# ECG_Schematic.net
KiCad netlist of a schematic drawn in Altium Designer
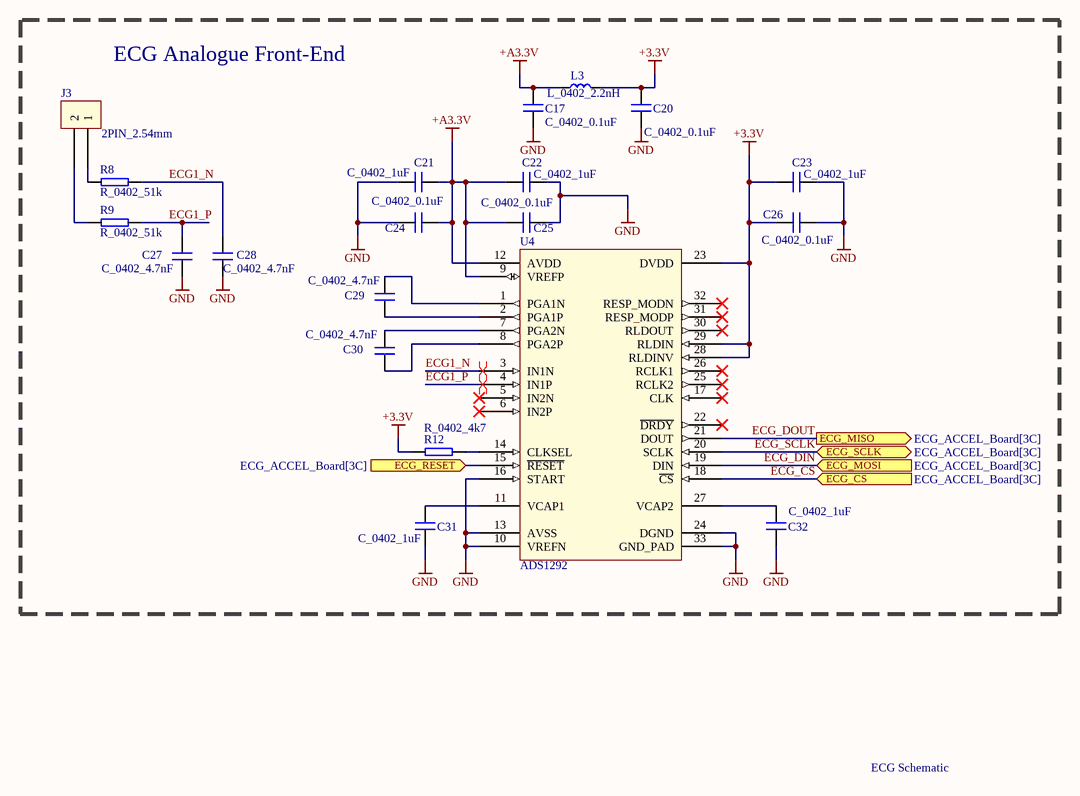
[diagram p0: ECG_Schematic.SchDoc]

(export (version "E")
  (design (tool "Eeschema 10.0.6"))
  (components
    (comp (ref "C17")
      (value "C_0402_0.1uF")
      (footprint "C_0402")
      (fields (field (name "JLC PART NUMBER") "C1525"))
      (libsource (lib "Petar B") (part "Cap_symbol"))
    )
    (comp (ref "C20")
      (value "C_0402_0.1uF")
      (footprint "C_0402")
      (fields (field (name "JLC PART NUMBER") "C1525"))
      (libsource (lib "Petar B") (part "Cap_symbol"))
    )
    (comp (ref "C21")
      (value "C_0402_1uF")
      (footprint "C_0402")
      (fields (field (name "JLC PART NUMBER") "C52923"))
      (libsource (lib "Petar B") (part "Cap_symbol"))
    )
    (comp (ref "C22")
      (value "C_0402_1uF")
      (footprint "C_0402")
      (fields (field (name "JLC PART NUMBER") "C52923"))
      (libsource (lib "Petar B") (part "Cap_symbol"))
    )
    (comp (ref "C23")
      (value "C_0402_1uF")
      (footprint "C_0402")
      (fields (field (name "JLC PART NUMBER") "C52923"))
      (libsource (lib "Petar B") (part "Cap_symbol"))
    )
    (comp (ref "C24")
      (value "C_0402_0.1uF")
      (footprint "C_0402")
      (fields (field (name "JLC PART NUMBER") "C1525"))
      (libsource (lib "Petar B") (part "Cap_symbol"))
    )
    (comp (ref "C25")
      (value "C_0402_0.1uF")
      (footprint "C_0402")
      (fields (field (name "JLC PART NUMBER") "C1525"))
      (libsource (lib "Petar B") (part "Cap_symbol"))
    )
    (comp (ref "C26")
      (value "C_0402_0.1uF")
      (footprint "C_0402")
      (fields (field (name "JLC PART NUMBER") "C1525"))
      (libsource (lib "Petar B") (part "Cap_symbol"))
    )
    (comp (ref "C27")
      (value "C_0402_4.7nF")
      (footprint "C_0402")
      (fields (field (name "JLC PART NUMBER") "C1538"))
      (libsource (lib "Petar B") (part "Cap_symbol"))
    )
    (comp (ref "C28")
      (value "C_0402_4.7nF")
      (footprint "C_0402")
      (fields (field (name "JLC PART NUMBER") "C1538"))
      (libsource (lib "Petar B") (part "Cap_symbol"))
    )
    (comp (ref "C29")
      (value "C_0402_4.7nF")
      (footprint "C_0402")
      (fields (field (name "JLC PART NUMBER") "C1538"))
      (libsource (lib "Petar B") (part "Cap_symbol"))
    )
    (comp (ref "C30")
      (value "C_0402_4.7nF")
      (footprint "C_0402")
      (fields (field (name "JLC PART NUMBER") "C1538"))
      (libsource (lib "Petar B") (part "Cap_symbol"))
    )
    (comp (ref "C31")
      (value "C_0402_1uF")
      (footprint "C_0402")
      (fields (field (name "JLC PART NUMBER") "C52923"))
      (libsource (lib "Petar B") (part "Cap_symbol"))
    )
    (comp (ref "C32")
      (value "C_0402_1uF")
      (footprint "C_0402")
      (fields (field (name "JLC PART NUMBER") "C52923"))
      (libsource (lib "Petar B") (part "Cap_symbol"))
    )
    (comp (ref "J3")
      (value "2PIN_2.54mm")
      (footprint "2PIN_2.54mm-Footprint-1")
      (description "2 pin power input")
      (fields (field (name "JLC PART NUMBER") "C5360898"))
      (libsource (lib "Petar B") (part "2PIN_2.54mm-Symbol-1"))
    )
    (comp (ref "L3")
      (value "L_0402_2.2nH")
      (footprint "L_0402")
      (fields (field (name "JLC PART NUMBER") "C92035"))
      (libsource (lib "Petar B") (part "Ind_Symbol"))
    )
    (comp (ref "R8")
      (value "R_0402_51k")
      (footprint "R_0402")
      (fields (field (name "JLC PART NUMBER") "C25794"))
      (libsource (lib "Petar B") (part "R_symbol"))
    )
    (comp (ref "R9")
      (value "R_0402_51k")
      (footprint "R_0402")
      (fields (field (name "JLC PART NUMBER") "C25794"))
      (libsource (lib "Petar B") (part "R_symbol"))
    )
    (comp (ref "R12")
      (value "R_0402_4k7")
      (footprint "R_0402")
      (fields (field (name "JLC PART NUMBER") "C25900"))
      (libsource (lib "Petar B") (part "R_symbol"))
    )
    (comp (ref "U4")
      (value "ADS1292")
      (footprint "QFN127P600-8N")
      (description "ECG Analog Front End - AFE 2-Channel,24B ADC")
      (fields (field (name "JLC PART NUMBER") "C456281"))
      (libsource (lib "Petar B") (part "ADS1292-Symbol-1"))
    )
  )
  (nets
    (net (code "1") (name "+3.3V") (class "Default")
      (node (ref "C20") (pin "2") (pinfunction "2_2") (pintype "passive"))
      (node (ref "C23") (pin "1") (pinfunction "1_1") (pintype "passive"))
      (node (ref "C26") (pin "1") (pinfunction "1_1") (pintype "passive"))
      (node (ref "L3") (pin "2") (pinfunction "2_2") (pintype "passive"))
      (node (ref "R12") (pin "2") (pinfunction "2_2") (pintype "passive"))
      (node (ref "U4") (pin "23") (pinfunction "DVDD_23") (pintype "power_in"))
      (node (ref "U4") (pin "28") (pinfunction "RLDINV_28") (pintype "input"))
      (node (ref "U4") (pin "29") (pinfunction "RLDIN_29") (pintype "input"))
    )
    (net (code "2") (name "+A3.3V") (class "Default")
      (node (ref "C17") (pin "2") (pinfunction "2_2") (pintype "passive"))
      (node (ref "C21") (pin "2") (pinfunction "2_2") (pintype "passive"))
      (node (ref "C22") (pin "2") (pinfunction "2_2") (pintype "passive"))
      (node (ref "C24") (pin "2") (pinfunction "2_2") (pintype "passive"))
      (node (ref "C25") (pin "2") (pinfunction "2_2") (pintype "passive"))
      (node (ref "L3") (pin "1") (pinfunction "1_1") (pintype "passive"))
      (node (ref "U4") (pin "12") (pinfunction "AVDD_12") (pintype "power_in"))
      (node (ref "U4") (pin "9") (pinfunction "VREFP_9") (pintype "bidirectional"))
    )
    (net (code "3") (name "/ECG1_N") (class "Default")
      (node (ref "C28") (pin "2") (pinfunction "2_2") (pintype "passive"))
      (node (ref "R8") (pin "1") (pinfunction "1_1") (pintype "passive"))
      (node (ref "U4") (pin "3") (pinfunction "IN1N_3") (pintype "input"))
    )
    (net (code "4") (name "/ECG1_P") (class "Default")
      (node (ref "C27") (pin "2") (pinfunction "2_2") (pintype "passive"))
      (node (ref "R9") (pin "1") (pinfunction "1_1") (pintype "passive"))
      (node (ref "U4") (pin "4") (pinfunction "IN1P_4") (pintype "input"))
    )
    (net (code "5") (name "/ECG_CS") (class "Default")
      (node (ref "U4") (pin "18") (pinfunction "~{CS}_18") (pintype "input"))
    )
    (net (code "6") (name "/ECG_DIN") (class "Default")
      (node (ref "U4") (pin "19") (pinfunction "DIN_19") (pintype "input"))
    )
    (net (code "7") (name "/ECG_DOUT") (class "Default")
      (node (ref "U4") (pin "21") (pinfunction "DOUT_21") (pintype "output"))
    )
    (net (code "8") (name "/ECG_RESET") (class "Default")
      (node (ref "U4") (pin "15") (pinfunction "~{RESET}_15") (pintype "input"))
    )
    (net (code "9") (name "/ECG_SCLK") (class "Default")
      (node (ref "U4") (pin "20") (pinfunction "SCLK_20") (pintype "input"))
    )
    (net (code "10") (name "GND") (class "Default")
      (node (ref "C17") (pin "1") (pinfunction "1_1") (pintype "passive"))
      (node (ref "C20") (pin "1") (pinfunction "1_1") (pintype "passive"))
      (node (ref "C21") (pin "1") (pinfunction "1_1") (pintype "passive"))
      (node (ref "C22") (pin "1") (pinfunction "1_1") (pintype "passive"))
      (node (ref "C23") (pin "2") (pinfunction "2_2") (pintype "passive"))
      (node (ref "C24") (pin "1") (pinfunction "1_1") (pintype "passive"))
      (node (ref "C25") (pin "1") (pinfunction "1_1") (pintype "passive"))
      (node (ref "C26") (pin "2") (pinfunction "2_2") (pintype "passive"))
      (node (ref "C27") (pin "1") (pinfunction "1_1") (pintype "passive"))
      (node (ref "C28") (pin "1") (pinfunction "1_1") (pintype "passive"))
      (node (ref "C31") (pin "1") (pinfunction "1_1") (pintype "passive"))
      (node (ref "C32") (pin "1") (pinfunction "1_1") (pintype "passive"))
      (node (ref "U4") (pin "10") (pinfunction "VREFN_10") (pintype "power_in"))
      (node (ref "U4") (pin "13") (pinfunction "AVSS_13") (pintype "power_in"))
      (node (ref "U4") (pin "16") (pinfunction "START_16") (pintype "input"))
      (node (ref "U4") (pin "24") (pinfunction "DGND_24") (pintype "power_in"))
      (node (ref "U4") (pin "33") (pinfunction "GND_PAD_33") (pintype "power_in"))
    )
    (net (code "11") (name "Net-(J3-Pad1)") (class "Default")
      (node (ref "J3") (pin "1") (pinfunction "1_1") (pintype "passive"))
      (node (ref "R8") (pin "2") (pinfunction "2_2") (pintype "passive"))
    )
    (net (code "12") (name "Net-(J3-Pad2)") (class "Default")
      (node (ref "J3") (pin "2") (pinfunction "2_2") (pintype "passive"))
      (node (ref "R9") (pin "2") (pinfunction "2_2") (pintype "passive"))
    )
    (net (code "13") (name "Net-(U4-CLKSEL)") (class "Default")
      (node (ref "R12") (pin "1") (pinfunction "1_1") (pintype "passive"))
      (node (ref "U4") (pin "14") (pinfunction "CLKSEL_14") (pintype "input"))
    )
    (net (code "14") (name "Net-(U4-PGA1N)") (class "Default")
      (node (ref "C29") (pin "2") (pinfunction "2_2") (pintype "passive"))
      (node (ref "U4") (pin "1") (pinfunction "PGA1N_1") (pintype "output"))
    )
    (net (code "15") (name "Net-(U4-PGA1P)") (class "Default")
      (node (ref "C29") (pin "1") (pinfunction "1_1") (pintype "passive"))
      (node (ref "U4") (pin "2") (pinfunction "PGA1P_2") (pintype "output"))
    )
    (net (code "16") (name "Net-(U4-PGA2N)") (class "Default")
      (node (ref "C30") (pin "2") (pinfunction "2_2") (pintype "passive"))
      (node (ref "U4") (pin "7") (pinfunction "PGA2N_7") (pintype "output"))
    )
    (net (code "17") (name "Net-(U4-PGA2P)") (class "Default")
      (node (ref "C30") (pin "1") (pinfunction "1_1") (pintype "passive"))
      (node (ref "U4") (pin "8") (pinfunction "PGA2P_8") (pintype "output"))
    )
    (net (code "18") (name "Net-(U4-VCAP1)") (class "Default")
      (node (ref "C31") (pin "2") (pinfunction "2_2") (pintype "passive"))
      (node (ref "U4") (pin "11") (pinfunction "VCAP1_11") (pintype "passive"))
    )
    (net (code "19") (name "Net-(U4-VCAP2)") (class "Default")
      (node (ref "C32") (pin "2") (pinfunction "2_2") (pintype "passive"))
      (node (ref "U4") (pin "27") (pinfunction "VCAP2_27") (pintype "passive"))
    )
    (net (code "20") (name "unconnected-(U4-CLK-Pad17)") (class "Default")
      (node (ref "U4") (pin "17") (pinfunction "CLK_17") (pintype "input+no_connect"))
    )
    (net (code "21") (name "unconnected-(U4-IN2N-Pad5)") (class "Default")
      (node (ref "U4") (pin "5") (pinfunction "IN2N_5") (pintype "input+no_connect"))
    )
    (net (code "22") (name "unconnected-(U4-IN2P-Pad6)") (class "Default")
      (node (ref "U4") (pin "6") (pinfunction "IN2P_6") (pintype "input+no_connect"))
    )
    (net (code "23") (name "unconnected-(U4-RCLK1-Pad26)") (class "Default")
      (node (ref "U4") (pin "26") (pinfunction "RCLK1_26") (pintype "output+no_connect"))
    )
    (net (code "24") (name "unconnected-(U4-RCLK2-Pad25)") (class "Default")
      (node (ref "U4") (pin "25") (pinfunction "RCLK2_25") (pintype "output+no_connect"))
    )
    (net (code "25") (name "unconnected-(U4-RESP_MODN-Pad32)") (class "Default")
      (node (ref "U4") (pin "32") (pinfunction "RESP_MODN_32") (pintype "output+no_connect"))
    )
    (net (code "26") (name "unconnected-(U4-RESP_MODP-Pad31)") (class "Default")
      (node (ref "U4") (pin "31") (pinfunction "RESP_MODP_31") (pintype "output+no_connect"))
    )
    (net (code "27") (name "unconnected-(U4-RLDOUT-Pad30)") (class "Default")
      (node (ref "U4") (pin "30") (pinfunction "RLDOUT_30") (pintype "output+no_connect"))
    )
    (net (code "28") (name "unconnected-(U4-~{DRDY}-Pad22)") (class "Default")
      (node (ref "U4") (pin "22") (pinfunction "~{DRDY}_22") (pintype "output+no_connect"))
    )
  )
)
